# 20dB_Attenuator_TX.net
KiCad netlist of a schematic drawn in Altium Designer
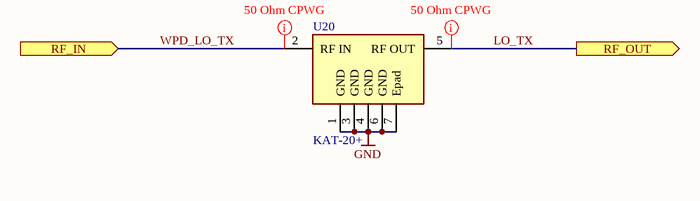
[diagram p0: 20dB_Attenuator_TX.SchDoc]

(export (version "E")
  (design (tool "Eeschema 10.0.6"))
  (components
    (comp (ref "U20")
      (value "KAT-20+")
      (footprint "MC1630-1")
      (fields (field (name "MANUFACTURER") "Minicircuits"))
      (libsource (lib "database_library") (part "KAT-XX+"))
    )
  )
  (nets
    (net (code "1") (name "/LO_TX") (class "Default")
      (node (ref "U20") (pin "5") (pinfunction "RF_OUT_5") (pintype "passive"))
    )
    (net (code "2") (name "/WPD_LO_TX") (class "Default")
      (node (ref "U20") (pin "2") (pinfunction "RF_IN_2") (pintype "passive"))
    )
    (net (code "3") (name "GND") (class "Default")
      (node (ref "U20") (pin "1") (pinfunction "GND_1") (pintype "passive"))
      (node (ref "U20") (pin "3") (pinfunction "GND_3") (pintype "passive"))
      (node (ref "U20") (pin "4") (pinfunction "GND_4") (pintype "passive"))
      (node (ref "U20") (pin "6") (pinfunction "GND_6") (pintype "passive"))
      (node (ref "U20") (pin "7") (pinfunction "Epad_7") (pintype "passive"))
    )
  )
)
